# CS3_Schnittstelle.net
KiCad netlist of a schematic drawn in EAGLE
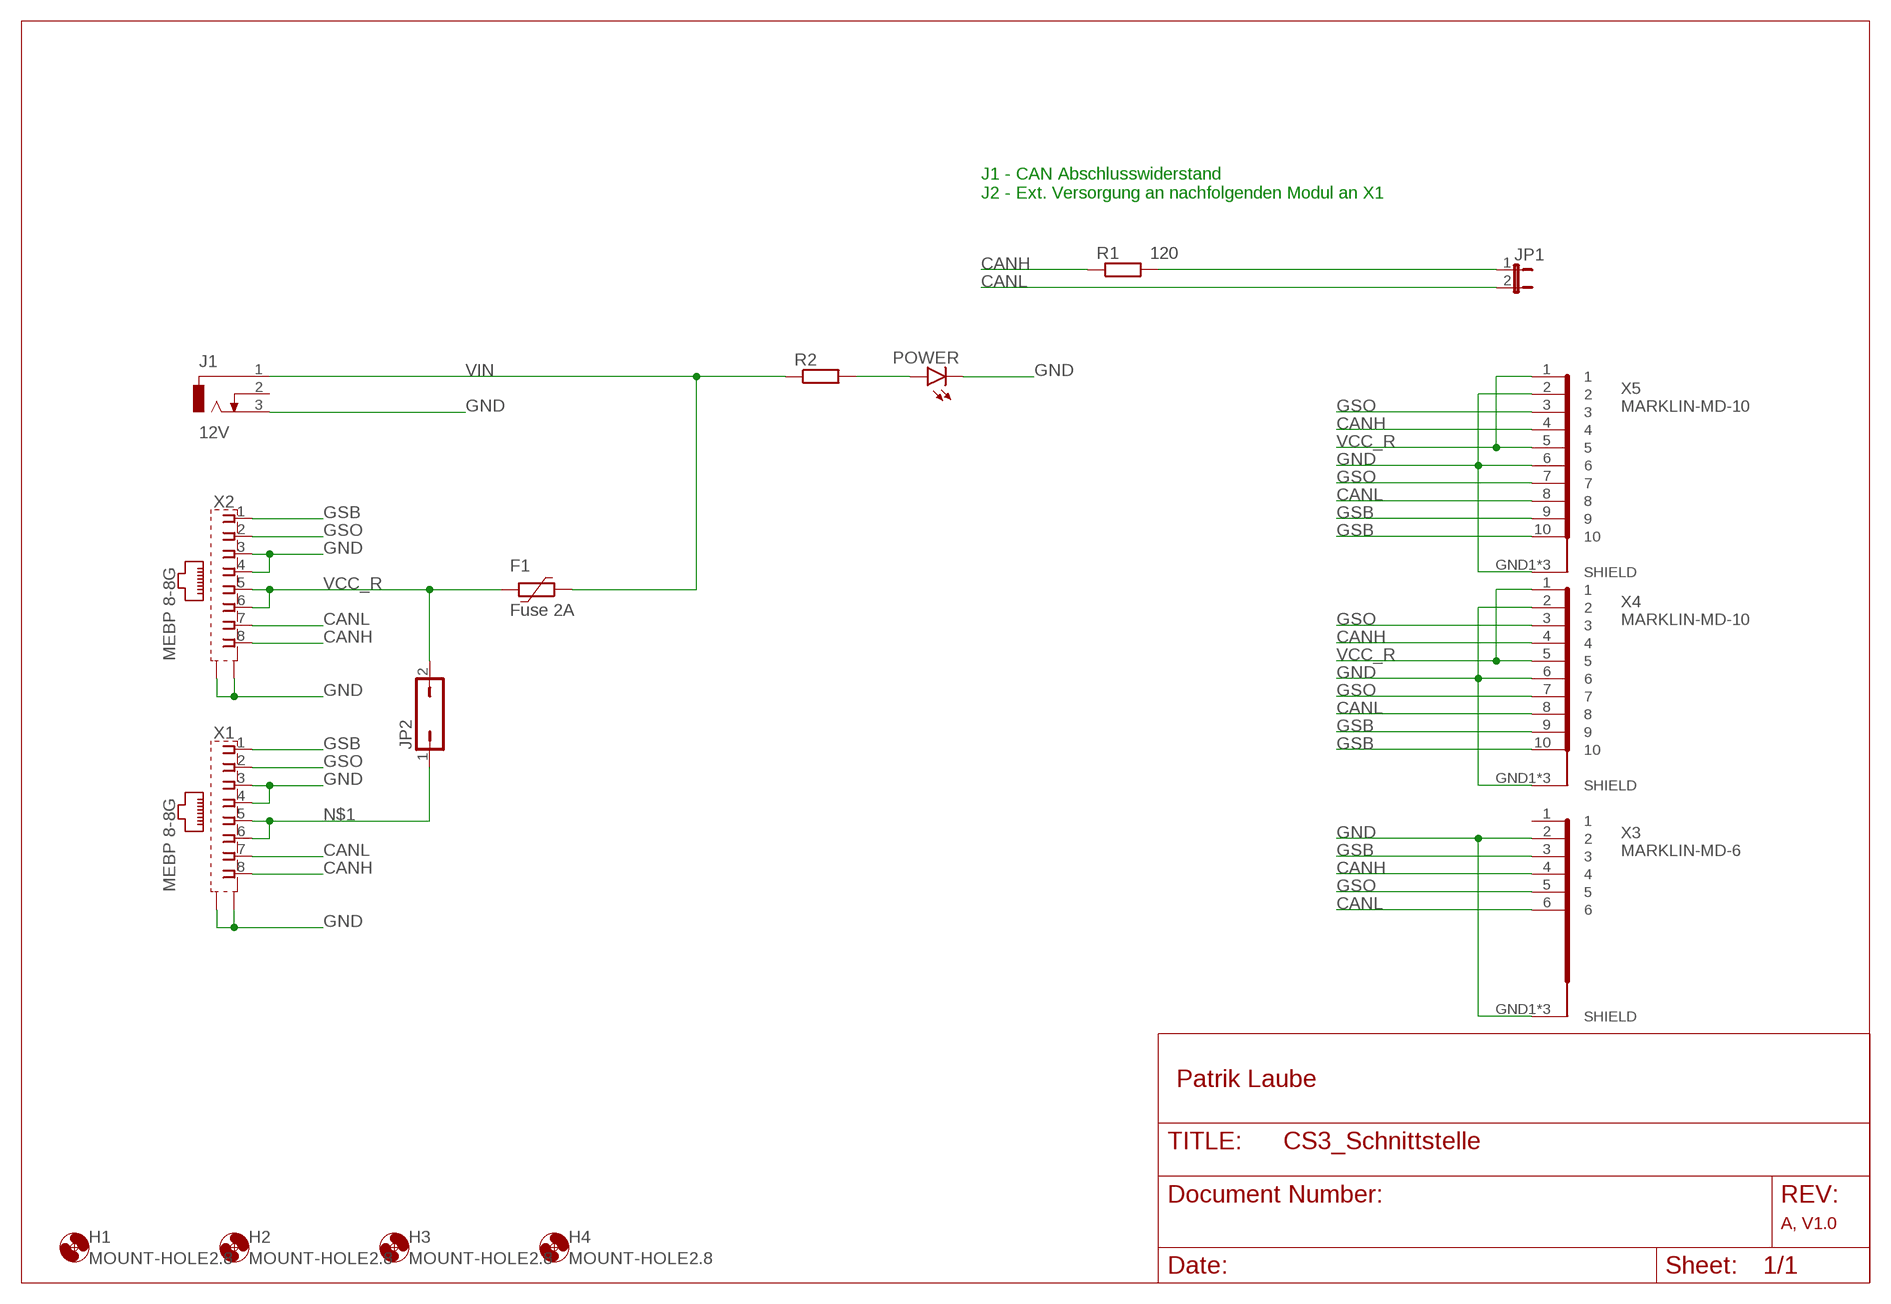
[diagram p0: schematic, sheet 1]

(export (version "E")
  (design (tool "Eeschema 10.0.6"))
  (components
    (comp (ref "F1")
      (value "Fuse 2A")
      (footprint "eagle-import:2920L")
      (fields (field (name "MF") "Littelfuse") (field (name "MPN") "2920L030"))
      (libsource (lib "eagle-import") (part "?2920L030"))
    )
    (comp (ref "H1")
      (value "MOUNT-HOLE2.8")
      (footprint "eagle-import:2,8")
      (libsource (lib "eagle-import") (part "MOUNT-HOLE2.8"))
    )
    (comp (ref "H2")
      (value "MOUNT-HOLE2.8")
      (footprint "eagle-import:2,8")
      (libsource (lib "eagle-import") (part "MOUNT-HOLE2.8"))
    )
    (comp (ref "H3")
      (value "MOUNT-HOLE2.8")
      (footprint "eagle-import:2,8")
      (libsource (lib "eagle-import") (part "MOUNT-HOLE2.8"))
    )
    (comp (ref "H4")
      (value "MOUNT-HOLE2.8")
      (footprint "eagle-import:2,8")
      (libsource (lib "eagle-import") (part "MOUNT-HOLE2.8"))
    )
    (comp (ref "J1")
      (value "12V")
      (footprint "eagle-import:DCJ0202")
      (libsource (lib "eagle-import") (part "DCJ0202"))
    )
    (comp (ref "JP1")
      (value "JP1E")
      (footprint "eagle-import:JP1")
      (libsource (lib "eagle-import") (part "JP1E"))
    )
    (comp (ref "JP2")
      (value "JP1Q")
      (footprint "eagle-import:JP1")
      (libsource (lib "eagle-import") (part "JP1Q"))
    )
    (comp (ref "POWER")
      (value "LEDCHIPLED_1206")
      (footprint "eagle-import:CHIPLED_1206")
      (libsource (lib "eagle-import") (part "LEDCHIPLED_1206"))
    )
    (comp (ref "R1")
      (value "120")
      (footprint "eagle-import:R1206")
      (libsource (lib "eagle-import") (part "R-EU_R1206"))
    )
    (comp (ref "R2")
      (value "R-EU_R1206")
      (footprint "eagle-import:R1206")
      (libsource (lib "eagle-import") (part "R-EU_R1206"))
    )
    (comp (ref "X1")
      (value "MEBP 8-8G")
      (footprint "eagle-import:XRJF-01A-0-D2A-010")
      (libsource (lib "eagle-import") (part "XRJFMEBP-8-8G-01A-0-D22-020"))
    )
    (comp (ref "X2")
      (value "MEBP 8-8G")
      (footprint "eagle-import:XRJF-01A-0-D2A-010")
      (libsource (lib "eagle-import") (part "XRJFMEBP-8-8G-01A-0-D22-020"))
    )
    (comp (ref "X3")
      (value "MARKLIN-MD-6")
      (footprint "eagle-import:MARKLIN-MD-6-PRINT")
      (libsource (lib "eagle-import") (part "MARKLIN-MD-6"))
    )
    (comp (ref "X4")
      (value "MARKLIN-MD-10")
      (footprint "eagle-import:MARKLIN-MD-10-PRINT")
      (libsource (lib "eagle-import") (part "MARKLIN-MD-10"))
    )
    (comp (ref "X5")
      (value "MARKLIN-MD-10")
      (footprint "eagle-import:MARKLIN-MD-10-PRINT")
      (libsource (lib "eagle-import") (part "MARKLIN-MD-10"))
    )
  )
  (nets
    (net (code "1") (name "/CANH") (class "Default")
      (node (ref "R1") (pin "1") (pinfunction "1_1") (pintype "passive"))
      (node (ref "X1") (pin "8") (pinfunction "8_8") (pintype "passive"))
      (node (ref "X2") (pin "8") (pinfunction "8_8") (pintype "passive"))
      (node (ref "X3") (pin "4") (pinfunction "4_4") (pintype "bidirectional"))
      (node (ref "X4") (pin "4") (pinfunction "4_4") (pintype "bidirectional"))
      (node (ref "X5") (pin "4") (pinfunction "4_4") (pintype "bidirectional"))
    )
    (net (code "2") (name "/CANL") (class "Default")
      (node (ref "JP1") (pin "2") (pinfunction "2_2") (pintype "passive"))
      (node (ref "X1") (pin "7") (pinfunction "7_7") (pintype "passive"))
      (node (ref "X2") (pin "7") (pinfunction "7_7") (pintype "passive"))
      (node (ref "X3") (pin "6") (pinfunction "6_6") (pintype "bidirectional"))
      (node (ref "X4") (pin "8") (pinfunction "8_8") (pintype "bidirectional"))
      (node (ref "X5") (pin "8") (pinfunction "8_8") (pintype "bidirectional"))
    )
    (net (code "3") (name "/GND") (class "Default")
      (node (ref "J1") (pin "3") (pinfunction "3_3") (pintype "passive"))
      (node (ref "POWER") (pin "C") (pinfunction "C_C") (pintype "passive"))
      (node (ref "X1") (pin "3") (pinfunction "3_3") (pintype "passive"))
      (node (ref "X1") (pin "4") (pinfunction "4_4") (pintype "passive"))
      (node (ref "X1") (pin "S1") (pinfunction "S_S1") (pintype "passive"))
      (node (ref "X1") (pin "S2") (pinfunction "S_S2") (pintype "passive"))
      (node (ref "X2") (pin "3") (pinfunction "3_3") (pintype "passive"))
      (node (ref "X2") (pin "4") (pinfunction "4_4") (pintype "passive"))
      (node (ref "X2") (pin "S1") (pinfunction "S_S1") (pintype "passive"))
      (node (ref "X2") (pin "S2") (pinfunction "S_S2") (pintype "passive"))
      (node (ref "X3") (pin "2") (pinfunction "2_2") (pintype "bidirectional"))
      (node (ref "X3") (pin "GND1") (pinfunction "SHIELD_GND1") (pintype "bidirectional"))
      (node (ref "X3") (pin "GND2") (pinfunction "SHIELD_GND2") (pintype "bidirectional"))
      (node (ref "X3") (pin "GND3") (pinfunction "SHIELD_GND3") (pintype "bidirectional"))
      (node (ref "X4") (pin "2") (pinfunction "2_2") (pintype "bidirectional"))
      (node (ref "X4") (pin "6") (pinfunction "6_6") (pintype "bidirectional"))
      (node (ref "X4") (pin "GND1") (pinfunction "SHIELD_GND1") (pintype "bidirectional"))
      (node (ref "X4") (pin "GND2") (pinfunction "SHIELD_GND2") (pintype "bidirectional"))
      (node (ref "X4") (pin "GND3") (pinfunction "SHIELD_GND3") (pintype "bidirectional"))
      (node (ref "X5") (pin "2") (pinfunction "2_2") (pintype "bidirectional"))
      (node (ref "X5") (pin "6") (pinfunction "6_6") (pintype "bidirectional"))
      (node (ref "X5") (pin "GND1") (pinfunction "SHIELD_GND1") (pintype "bidirectional"))
      (node (ref "X5") (pin "GND2") (pinfunction "SHIELD_GND2") (pintype "bidirectional"))
      (node (ref "X5") (pin "GND3") (pinfunction "SHIELD_GND3") (pintype "bidirectional"))
    )
    (net (code "4") (name "/GSB") (class "Default")
      (node (ref "X1") (pin "1") (pinfunction "1_1") (pintype "passive"))
      (node (ref "X2") (pin "1") (pinfunction "1_1") (pintype "passive"))
      (node (ref "X3") (pin "3") (pinfunction "3_3") (pintype "bidirectional"))
      (node (ref "X4") (pin "10") (pinfunction "10_10") (pintype "bidirectional"))
      (node (ref "X4") (pin "9") (pinfunction "9_9") (pintype "bidirectional"))
      (node (ref "X5") (pin "10") (pinfunction "10_10") (pintype "bidirectional"))
      (node (ref "X5") (pin "9") (pinfunction "9_9") (pintype "bidirectional"))
    )
    (net (code "5") (name "/GSO") (class "Default")
      (node (ref "X1") (pin "2") (pinfunction "2_2") (pintype "passive"))
      (node (ref "X2") (pin "2") (pinfunction "2_2") (pintype "passive"))
      (node (ref "X3") (pin "5") (pinfunction "5_5") (pintype "bidirectional"))
      (node (ref "X4") (pin "3") (pinfunction "3_3") (pintype "bidirectional"))
      (node (ref "X4") (pin "7") (pinfunction "7_7") (pintype "bidirectional"))
      (node (ref "X5") (pin "3") (pinfunction "3_3") (pintype "bidirectional"))
      (node (ref "X5") (pin "7") (pinfunction "7_7") (pintype "bidirectional"))
    )
    (net (code "6") (name "/N$1") (class "Default")
      (node (ref "JP2") (pin "1") (pinfunction "1_1") (pintype "passive"))
      (node (ref "X1") (pin "5") (pinfunction "5_5") (pintype "passive"))
      (node (ref "X1") (pin "6") (pinfunction "6_6") (pintype "passive"))
    )
    (net (code "7") (name "/VCC_R") (class "Default")
      (node (ref "F1") (pin "2") (pinfunction "2_2") (pintype "passive"))
      (node (ref "JP2") (pin "2") (pinfunction "2_2") (pintype "passive"))
      (node (ref "X2") (pin "5") (pinfunction "5_5") (pintype "passive"))
      (node (ref "X2") (pin "6") (pinfunction "6_6") (pintype "passive"))
      (node (ref "X4") (pin "1") (pinfunction "1_1") (pintype "bidirectional"))
      (node (ref "X4") (pin "5") (pinfunction "5_5") (pintype "bidirectional"))
      (node (ref "X5") (pin "1") (pinfunction "1_1") (pintype "bidirectional"))
      (node (ref "X5") (pin "5") (pinfunction "5_5") (pintype "bidirectional"))
    )
    (net (code "8") (name "/VIN") (class "Default")
      (node (ref "F1") (pin "1") (pinfunction "1_1") (pintype "passive"))
      (node (ref "J1") (pin "1") (pinfunction "1_1") (pintype "passive"))
      (node (ref "R2") (pin "1") (pinfunction "1_1") (pintype "passive"))
    )
    (net (code "9") (name "Net-(JP1-Pad1)") (class "Default")
      (node (ref "JP1") (pin "1") (pinfunction "1_1") (pintype "passive"))
      (node (ref "R1") (pin "2") (pinfunction "2_2") (pintype "passive"))
    )
    (net (code "10") (name "Net-(POWER-PadA)") (class "Default")
      (node (ref "POWER") (pin "A") (pinfunction "A_A") (pintype "passive"))
      (node (ref "R2") (pin "2") (pinfunction "2_2") (pintype "passive"))
    )
    (net (code "11") (name "unconnected-(J1-Pad2)") (class "Default")
      (node (ref "J1") (pin "2") (pinfunction "2_2") (pintype "passive"))
    )
    (net (code "12") (name "unconnected-(X3-Pad1)") (class "Default")
      (node (ref "X3") (pin "1") (pinfunction "1_1") (pintype "bidirectional"))
    )
  )
)
